# DAC.net
KiCad netlist of a schematic drawn in Altium Designer
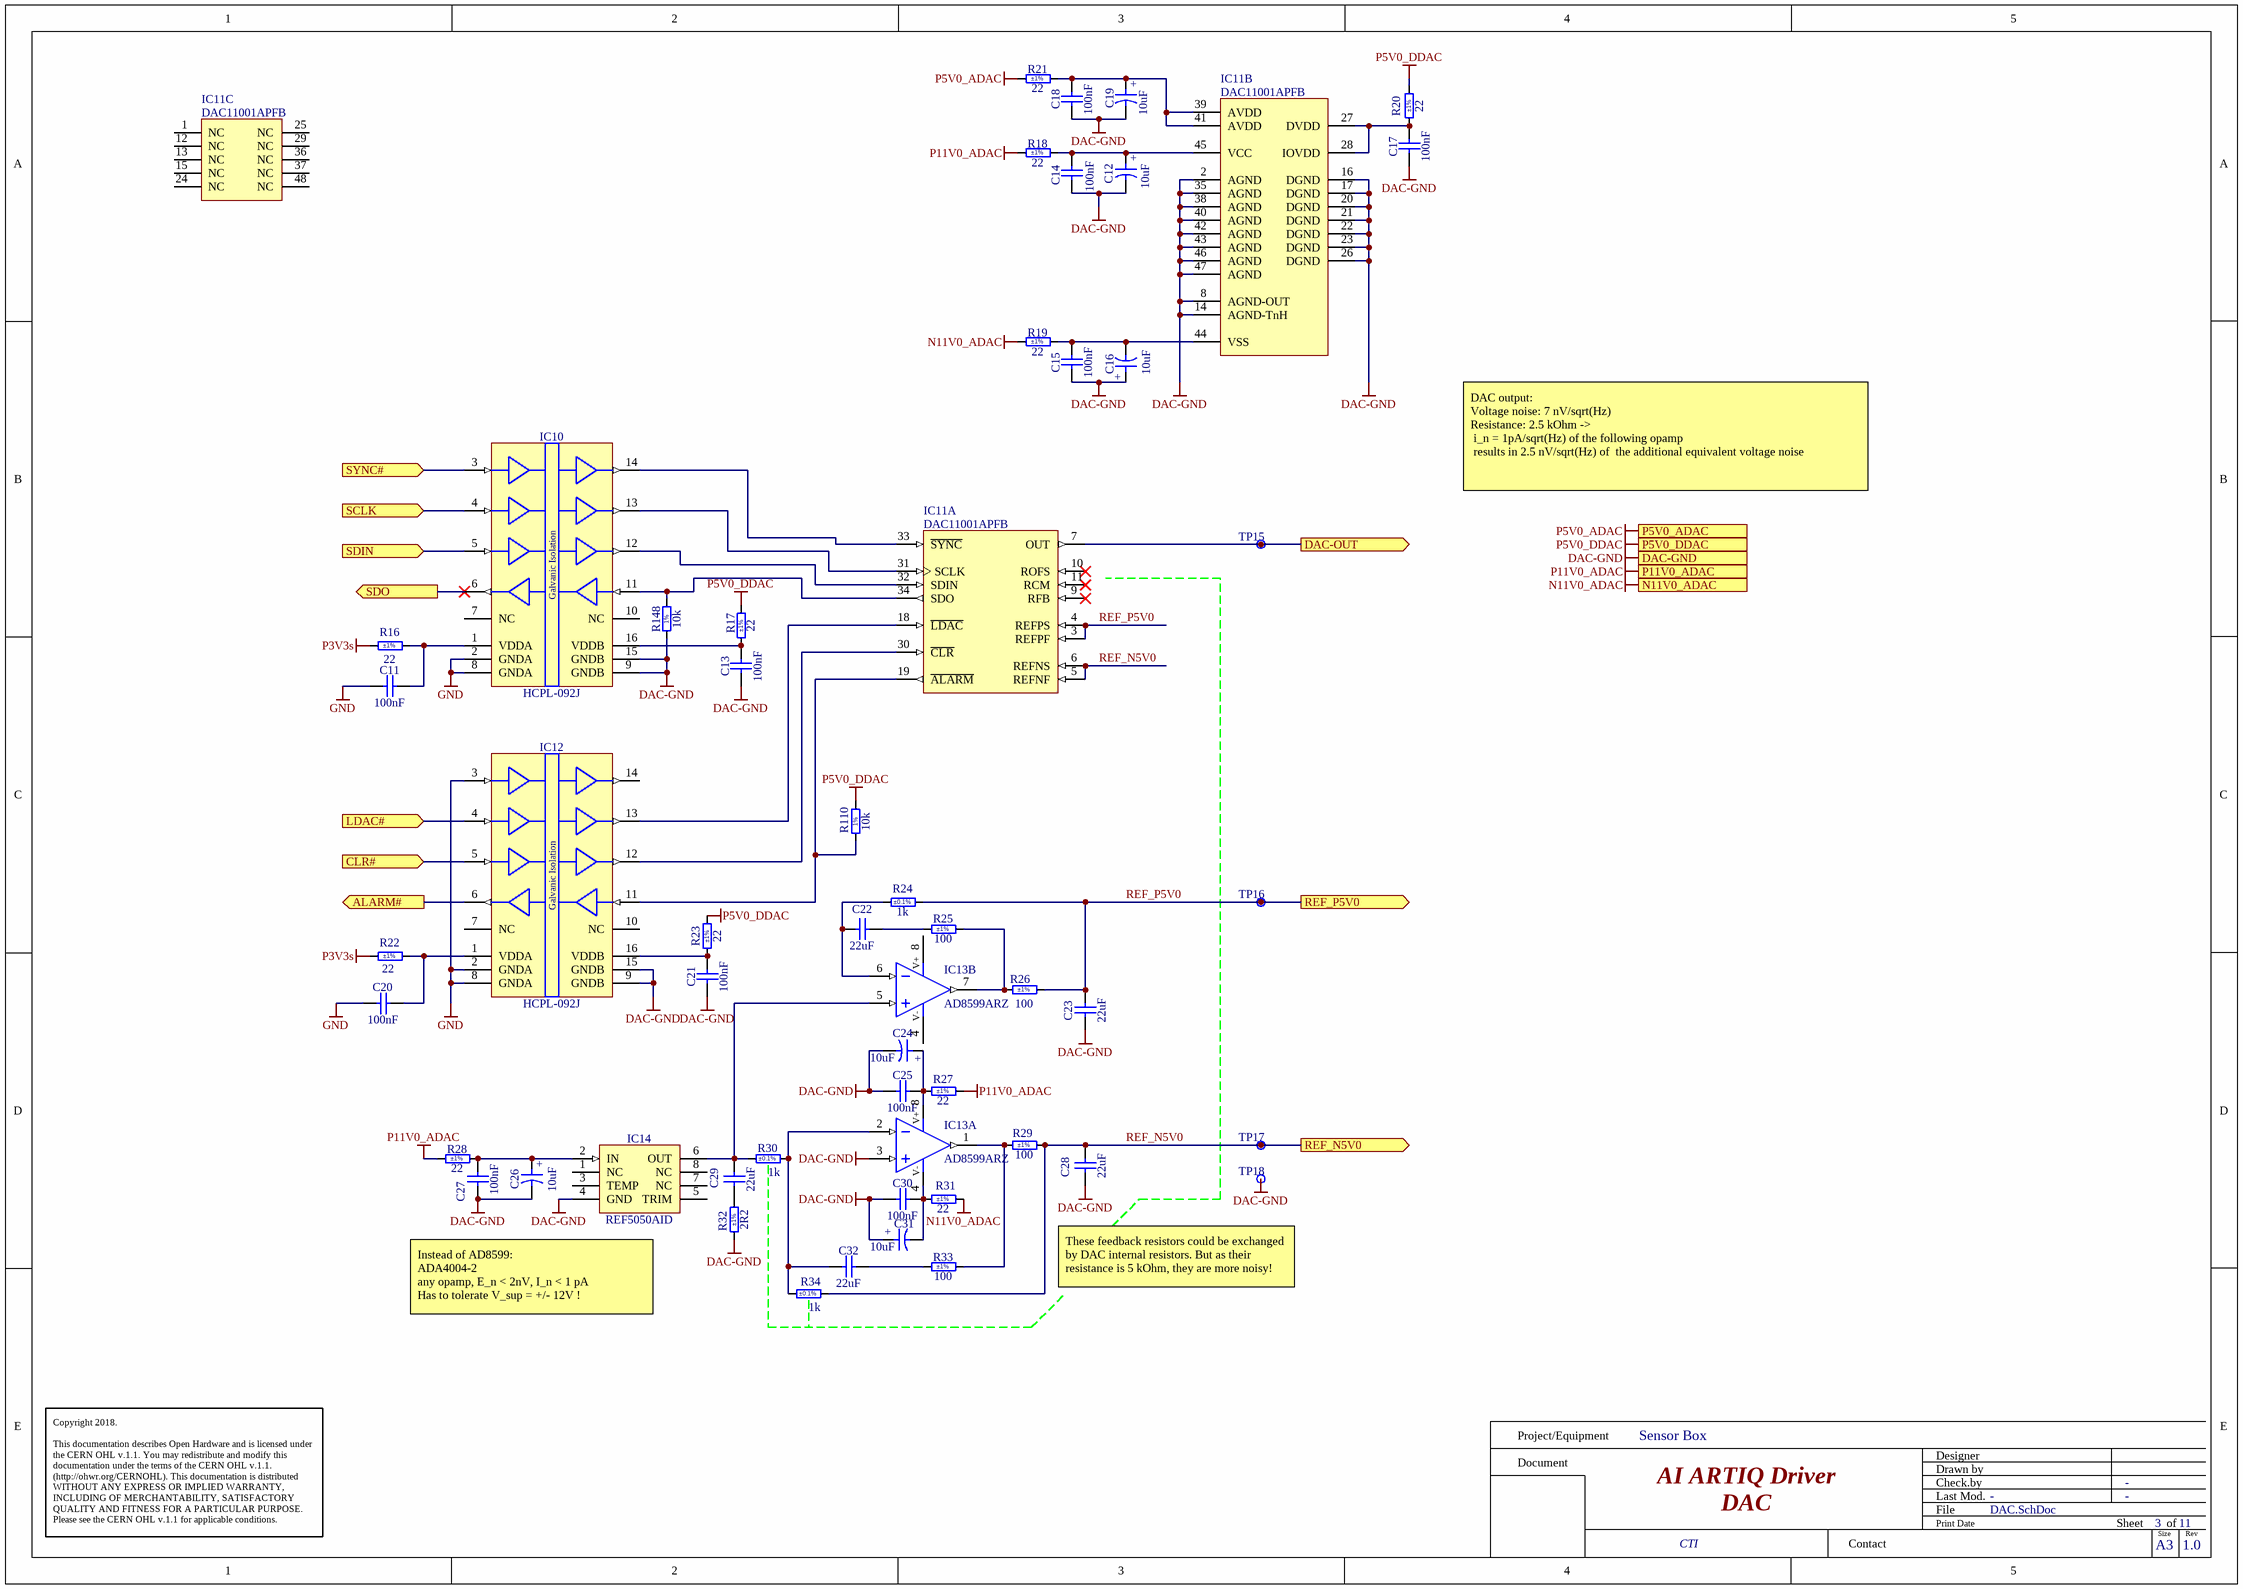
[diagram p0: DAC.SchDoc]

(export (version "E")
  (design (tool "Eeschema 10.0.6"))
  (components
    (comp (ref "C11")
      (value "100nF")
      (footprint "CAPC1608X87N")
      (description "Non-polarised capacitor")
      (fields
        (field (name "PART NUMBER") "CC0603_100NF_50V_10%_X7R")
        (field (name "VOLTAGE") "50V")
        (field (name "AUTHOR") "CERN DEM JLC")
      )
      (libsource (lib "Capacitors") (part "Capacitor - non polarized"))
    )
    (comp (ref "C12")
      (value "10uF")
      (footprint "CAPMP3528X210N")
      (description "Polarised capacitor")
      (fields
        (field (name "PART NUMBER") "CTE3528-21_10UF_20V_10%_AVX_TPSB106K020T0500")
        (field (name "VOLTAGE") "20V")
        (field (name "AUTHOR") "CERN DEM JLC")
      )
      (libsource (lib "Capacitors") (part "Capacitor - polarized"))
    )
    (comp (ref "C13")
      (value "100nF")
      (footprint "CAPC1608X87N")
      (description "Non-polarised capacitor")
      (fields
        (field (name "PART NUMBER") "CC0603_100NF_50V_10%_X7R")
        (field (name "VOLTAGE") "50V")
        (field (name "AUTHOR") "CERN DEM JLC")
      )
      (libsource (lib "Capacitors") (part "Capacitor - non polarized"))
    )
    (comp (ref "C14")
      (value "100nF")
      (footprint "CAPC1005X55N")
      (description "Non-polarised capacitor")
      (fields
        (field (name "PART NUMBER") "CC0402_100NF_50V_10%_X7R")
        (field (name "VOLTAGE") "50V")
        (field (name "AUTHOR") "CERN DEM MR")
      )
      (libsource (lib "Capacitors") (part "Capacitor - non polarized"))
    )
    (comp (ref "C15")
      (value "100nF")
      (footprint "CAPC1005X55N")
      (description "Non-polarised capacitor")
      (fields
        (field (name "PART NUMBER") "CC0402_100NF_50V_10%_X7R")
        (field (name "VOLTAGE") "50V")
        (field (name "AUTHOR") "CERN DEM MR")
      )
      (libsource (lib "Capacitors") (part "Capacitor - non polarized"))
    )
    (comp (ref "C16")
      (value "10uF")
      (footprint "CAPMP3528X210N")
      (description "Polarised capacitor")
      (fields
        (field (name "PART NUMBER") "CTE3528-21_10UF_20V_10%_AVX_TPSB106K020T0500")
        (field (name "VOLTAGE") "20V")
        (field (name "AUTHOR") "CERN DEM JLC")
      )
      (libsource (lib "Capacitors") (part "Capacitor - polarized"))
    )
    (comp (ref "C17")
      (value "100nF")
      (footprint "CAPC1005X55N")
      (description "Non-polarised capacitor")
      (fields
        (field (name "PART NUMBER") "CC0402_100NF_50V_10%_X7R")
        (field (name "VOLTAGE") "50V")
        (field (name "AUTHOR") "CERN DEM MR")
      )
      (libsource (lib "Capacitors") (part "Capacitor - non polarized"))
    )
    (comp (ref "C18")
      (value "100nF")
      (footprint "CAPC1005X55N")
      (description "Non-polarised capacitor")
      (fields
        (field (name "PART NUMBER") "CC0402_100NF_50V_10%_X7R")
        (field (name "VOLTAGE") "50V")
        (field (name "AUTHOR") "CERN DEM MR")
      )
      (libsource (lib "Capacitors") (part "Capacitor - non polarized"))
    )
    (comp (ref "C19")
      (value "10uF")
      (footprint "CAPMP3528X210N")
      (description "Polarised capacitor")
      (fields
        (field (name "PART NUMBER") "CTE3528-21_10UF_20V_10%_AVX_TPSB106K020T0500")
        (field (name "VOLTAGE") "20V")
        (field (name "AUTHOR") "CERN DEM JLC")
      )
      (libsource (lib "Capacitors") (part "Capacitor - polarized"))
    )
    (comp (ref "C20")
      (value "100nF")
      (footprint "CAPC1608X87N")
      (description "Non-polarised capacitor")
      (fields
        (field (name "PART NUMBER") "CC0603_100NF_50V_10%_X7R")
        (field (name "VOLTAGE") "50V")
        (field (name "AUTHOR") "CERN DEM JLC")
      )
      (libsource (lib "Capacitors") (part "Capacitor - non polarized"))
    )
    (comp (ref "C21")
      (value "100nF")
      (footprint "CAPC1608X87N")
      (description "Non-polarised capacitor")
      (fields
        (field (name "PART NUMBER") "CC0603_100NF_50V_10%_X7R")
        (field (name "VOLTAGE") "50V")
        (field (name "AUTHOR") "CERN DEM JLC")
      )
      (libsource (lib "Capacitors") (part "Capacitor - non polarized"))
    )
    (comp (ref "C22")
      (value "22uF")
      (footprint "CAPC2012X135N")
      (description "Non-polarised capacitor")
      (fields
        (field (name "PART NUMBER") "CC0805_22UF_16V_10%_X5R")
        (field (name "VOLTAGE") "16V")
        (field (name "AUTHOR") "CERN DEM JLC")
      )
      (libsource (lib "Capacitors") (part "Capacitor - non polarized"))
    )
    (comp (ref "C23")
      (value "22uF")
      (footprint "CAPC2012X135N")
      (description "Non-polarised capacitor")
      (fields
        (field (name "PART NUMBER") "CC0805_22UF_16V_10%_X5R")
        (field (name "VOLTAGE") "16V")
        (field (name "AUTHOR") "CERN DEM JLC")
      )
      (libsource (lib "Capacitors") (part "Capacitor - non polarized"))
    )
    (comp (ref "C24")
      (value "10uF")
      (footprint "CAPMP3528X210N")
      (description "Polarised capacitor")
      (fields
        (field (name "PART NUMBER") "CTE3528-21_10UF_20V_10%_AVX_TPSB106K020T0500")
        (field (name "VOLTAGE") "20V")
        (field (name "AUTHOR") "CERN DEM JLC")
      )
      (libsource (lib "Capacitors") (part "Capacitor - polarized"))
    )
    (comp (ref "C25")
      (value "100nF")
      (footprint "CAPC1608X87N")
      (description "Non-polarised capacitor")
      (fields
        (field (name "PART NUMBER") "CC0603_100NF_50V_10%_X7R")
        (field (name "VOLTAGE") "50V")
        (field (name "AUTHOR") "CERN DEM JLC")
      )
      (libsource (lib "Capacitors") (part "Capacitor - non polarized"))
    )
    (comp (ref "C26")
      (value "10uF")
      (footprint "CAPMP3528X210N")
      (description "Polarised capacitor")
      (fields
        (field (name "PART NUMBER") "CTE3528-21_10UF_20V_10%_AVX_TPSB106K020T0500")
        (field (name "VOLTAGE") "20V")
        (field (name "AUTHOR") "CERN DEM JLC")
      )
      (libsource (lib "Capacitors") (part "Capacitor - polarized"))
    )
    (comp (ref "C27")
      (value "100nF")
      (footprint "CAPC1608X87N")
      (description "Non-polarised capacitor")
      (fields
        (field (name "PART NUMBER") "CC0603_100NF_50V_10%_X7R")
        (field (name "VOLTAGE") "50V")
        (field (name "AUTHOR") "CERN DEM JLC")
      )
      (libsource (lib "Capacitors") (part "Capacitor - non polarized"))
    )
    (comp (ref "C28")
      (value "22uF")
      (footprint "CAPC2012X135N")
      (description "Non-polarised capacitor")
      (fields
        (field (name "PART NUMBER") "CC0805_22UF_16V_10%_X5R")
        (field (name "VOLTAGE") "16V")
        (field (name "AUTHOR") "CERN DEM JLC")
      )
      (libsource (lib "Capacitors") (part "Capacitor - non polarized"))
    )
    (comp (ref "C29")
      (value "22uF")
      (footprint "CAPC2012X135N")
      (description "Non-polarised capacitor")
      (fields
        (field (name "PART NUMBER") "CC0805_22UF_16V_10%_X5R")
        (field (name "VOLTAGE") "16V")
        (field (name "AUTHOR") "CERN DEM JLC")
      )
      (libsource (lib "Capacitors") (part "Capacitor - non polarized"))
    )
    (comp (ref "C30")
      (value "100nF")
      (footprint "CAPC1608X87N")
      (description "Non-polarised capacitor")
      (fields
        (field (name "PART NUMBER") "CC0603_100NF_50V_10%_X7R")
        (field (name "VOLTAGE") "50V")
        (field (name "AUTHOR") "CERN DEM JLC")
      )
      (libsource (lib "Capacitors") (part "Capacitor - non polarized"))
    )
    (comp (ref "C31")
      (value "10uF")
      (footprint "CAPMP3528X210N")
      (description "Polarised capacitor")
      (fields
        (field (name "PART NUMBER") "CTE3528-21_10UF_20V_10%_AVX_TPSB106K020T0500")
        (field (name "VOLTAGE") "20V")
        (field (name "AUTHOR") "CERN DEM JLC")
      )
      (libsource (lib "Capacitors") (part "Capacitor - polarized"))
    )
    (comp (ref "C32")
      (value "22uF")
      (footprint "CAPC2012X135N")
      (description "Non-polarised capacitor")
      (fields
        (field (name "PART NUMBER") "CC0805_22UF_16V_10%_X5R")
        (field (name "VOLTAGE") "16V")
        (field (name "AUTHOR") "CERN DEM JLC")
      )
      (libsource (lib "Capacitors") (part "Capacitor - non polarized"))
    )
    (comp (ref "IC10")
      (value "HCPL-092J")
      (footprint "HCPL-092J")
      (description "High Speed Digital Isolators Quad, 1/3, Bidirectional")
      (fields (field (name "MANUFACTURER") "BROADCOM") (field (name "AUTHOR") "CERN DEM HF"))
      (libsource (lib "ICs And Semiconductors") (part "HCPL-092J"))
    )
    (comp (ref "IC11")
      (value "DAC11001APFB")
      (footprint "QFP50P900X900X120-48N")
      (fields (field (name "MANUFACTURER") "TEXAS INSTRUMENTS") (field (name "AUTHOR") "CERN DEM HF"))
      (libsource (lib "ICs And Semiconductors") (part "DAC11001APFB"))
    )
    (comp (ref "IC12")
      (value "HCPL-092J")
      (footprint "HCPL-092J")
      (description "High Speed Digital Isolators Quad, 1/3, Bidirectional")
      (fields (field (name "MANUFACTURER") "BROADCOM") (field (name "AUTHOR") "CERN DEM HF"))
      (libsource (lib "ICs And Semiconductors") (part "HCPL-092J"))
    )
    (comp (ref "IC13")
      (value "AD8599ARZ")
      (footprint "SOIC127P600X175-8N")
      (description "Dual Operational Amplifier")
      (fields
        (field (name "MANUFACTURER") "ANALOG DEVICES")
        (field (name "MANUFACTURER PART NUMBER") "AD8599AR")
        (field (name "AUTHOR") "CERN DEM BC")
      )
      (libsource (lib "ICs And Semiconductors") (part "Operational Amplifier x2 Type1"))
    )
    (comp (ref "IC14")
      (value "REF5050AID")
      (footprint "SOIC127P600X175-8N")
      (description "Low-Noise, Very Low Drift, Precision Voltage Reference")
      (fields (field (name "MANUFACTURER") "TEXAS INSTRUMENTS") (field (name "AUTHOR") "CERN DEM HF"))
      (libsource (lib "ICs And Semiconductors") (part "REF50xx"))
    )
    (comp (ref "R16")
      (value "22")
      (footprint "RESC1608X55N")
      (description "Resistor - 1%")
      (fields
        (field (name "TOLERANCE") "±1%")
        (field (name "PART NUMBER") "R0603_22R_1%_0.1W_100PPM")
        (field (name "POWER") "0.1W")
        (field (name "AUTHOR") "CERN DEM JLC")
      )
      (libsource (lib "Resistors") (part "Resistor - 1%"))
    )
    (comp (ref "R17")
      (value "22")
      (footprint "RESC1608X55N")
      (description "Resistor - 1%")
      (fields
        (field (name "TOLERANCE") "±1%")
        (field (name "PART NUMBER") "R0603_22R_1%_0.1W_100PPM")
        (field (name "POWER") "0.1W")
        (field (name "AUTHOR") "CERN DEM JLC")
      )
      (libsource (lib "Resistors") (part "Resistor - 1%"))
    )
    (comp (ref "R18")
      (value "22")
      (footprint "RESC1608X55N")
      (description "Resistor - 1%")
      (fields
        (field (name "TOLERANCE") "±1%")
        (field (name "PART NUMBER") "R0603_22R_1%_0.1W_100PPM")
        (field (name "POWER") "0.1W")
        (field (name "AUTHOR") "CERN DEM JLC")
      )
      (libsource (lib "Resistors") (part "Resistor - 1%"))
    )
    (comp (ref "R19")
      (value "22")
      (footprint "RESC1608X55N")
      (description "Resistor - 1%")
      (fields
        (field (name "TOLERANCE") "±1%")
        (field (name "PART NUMBER") "R0603_22R_1%_0.1W_100PPM")
        (field (name "POWER") "0.1W")
        (field (name "AUTHOR") "CERN DEM JLC")
      )
      (libsource (lib "Resistors") (part "Resistor - 1%"))
    )
    (comp (ref "R20")
      (value "22")
      (footprint "RESC1608X55N")
      (description "Resistor - 1%")
      (fields
        (field (name "TOLERANCE") "±1%")
        (field (name "PART NUMBER") "R0603_22R_1%_0.1W_100PPM")
        (field (name "POWER") "0.1W")
        (field (name "AUTHOR") "CERN DEM JLC")
      )
      (libsource (lib "Resistors") (part "Resistor - 1%"))
    )
    (comp (ref "R21")
      (value "22")
      (footprint "RESC1608X55N")
      (description "Resistor - 1%")
      (fields
        (field (name "TOLERANCE") "±1%")
        (field (name "PART NUMBER") "R0603_22R_1%_0.1W_100PPM")
        (field (name "POWER") "0.1W")
        (field (name "AUTHOR") "CERN DEM JLC")
      )
      (libsource (lib "Resistors") (part "Resistor - 1%"))
    )
    (comp (ref "R22")
      (value "22")
      (footprint "RESC1608X55N")
      (description "Resistor - 1%")
      (fields
        (field (name "TOLERANCE") "±1%")
        (field (name "PART NUMBER") "R0603_22R_1%_0.1W_100PPM")
        (field (name "POWER") "0.1W")
        (field (name "AUTHOR") "CERN DEM JLC")
      )
      (libsource (lib "Resistors") (part "Resistor - 1%"))
    )
    (comp (ref "R23")
      (value "22")
      (footprint "RESC1608X55N")
      (description "Resistor - 1%")
      (fields
        (field (name "TOLERANCE") "±1%")
        (field (name "PART NUMBER") "R0603_22R_1%_0.1W_100PPM")
        (field (name "POWER") "0.1W")
        (field (name "AUTHOR") "CERN DEM JLC")
      )
      (libsource (lib "Resistors") (part "Resistor - 1%"))
    )
    (comp (ref "R24")
      (value "1k")
      (footprint "RESC1608X64N")
      (description "Resistor - 0.1%")
      (fields
        (field (name "TOLERANCE") "±0.1%")
        (field (name "PART NUMBER") "R0603_1K_0.1%_0.1W_25PPM")
        (field (name "POWER") "0.1W")
        (field (name "AUTHOR") "CERN DEM JLC")
      )
      (libsource (lib "Resistors") (part "Resistor - 0.1%"))
    )
    (comp (ref "R25")
      (value "100")
      (footprint "RESC1608X55N")
      (description "Resistor - 1%")
      (fields
        (field (name "TOLERANCE") "±1%")
        (field (name "PART NUMBER") "R0603_100R_1%_0.1W_100PPM")
        (field (name "POWER") "0.1W")
        (field (name "AUTHOR") "CERN DEM JLC")
      )
      (libsource (lib "Resistors") (part "Resistor - 1%"))
    )
    (comp (ref "R26")
      (value "100")
      (footprint "RESC1608X55N")
      (description "Resistor - 1%")
      (fields
        (field (name "TOLERANCE") "±1%")
        (field (name "PART NUMBER") "R0603_100R_1%_0.1W_100PPM")
        (field (name "POWER") "0.1W")
        (field (name "AUTHOR") "CERN DEM JLC")
      )
      (libsource (lib "Resistors") (part "Resistor - 1%"))
    )
    (comp (ref "R27")
      (value "22")
      (footprint "RESC1608X55N")
      (description "Resistor - 1%")
      (fields
        (field (name "TOLERANCE") "±1%")
        (field (name "PART NUMBER") "R0603_22R_1%_0.1W_100PPM")
        (field (name "POWER") "0.1W")
        (field (name "AUTHOR") "CERN DEM JLC")
      )
      (libsource (lib "Resistors") (part "Resistor - 1%"))
    )
    (comp (ref "R28")
      (value "22")
      (footprint "RESC1608X55N")
      (description "Resistor - 1%")
      (fields
        (field (name "TOLERANCE") "±1%")
        (field (name "PART NUMBER") "R0603_22R_1%_0.1W_100PPM")
        (field (name "POWER") "0.1W")
        (field (name "AUTHOR") "CERN DEM JLC")
      )
      (libsource (lib "Resistors") (part "Resistor - 1%"))
    )
    (comp (ref "R29")
      (value "100")
      (footprint "RESC1608X55N")
      (description "Resistor - 1%")
      (fields
        (field (name "TOLERANCE") "±1%")
        (field (name "PART NUMBER") "R0603_100R_1%_0.1W_100PPM")
        (field (name "POWER") "0.1W")
        (field (name "AUTHOR") "CERN DEM JLC")
      )
      (libsource (lib "Resistors") (part "Resistor - 1%"))
    )
    (comp (ref "R30")
      (value "1k")
      (footprint "RESC1608X64N")
      (description "Resistor - 0.1%")
      (fields
        (field (name "TOLERANCE") "±0.1%")
        (field (name "PART NUMBER") "R0603_1K_0.1%_0.1W_25PPM")
        (field (name "POWER") "0.1W")
        (field (name "AUTHOR") "CERN DEM JLC")
      )
      (libsource (lib "Resistors") (part "Resistor - 0.1%"))
    )
    (comp (ref "R31")
      (value "22")
      (footprint "RESC1608X55N")
      (description "Resistor - 1%")
      (fields
        (field (name "TOLERANCE") "±1%")
        (field (name "PART NUMBER") "R0603_22R_1%_0.1W_100PPM")
        (field (name "POWER") "0.1W")
        (field (name "AUTHOR") "CERN DEM JLC")
      )
      (libsource (lib "Resistors") (part "Resistor - 1%"))
    )
    (comp (ref "R32")
      (value "2R2")
      (footprint "RESC1608X55N")
      (description "Resistor - 1%")
      (fields
        (field (name "TOLERANCE") "±1%")
        (field (name "PART NUMBER") "R0603_2R2_1%_0.1W_200PPM")
        (field (name "POWER") "0.1W")
        (field (name "AUTHOR") "CERN DEM JLC")
      )
      (libsource (lib "Resistors") (part "Resistor - 1%"))
    )
    (comp (ref "R33")
      (value "100")
      (footprint "RESC1608X55N")
      (description "Resistor - 1%")
      (fields
        (field (name "TOLERANCE") "±1%")
        (field (name "PART NUMBER") "R0603_100R_1%_0.1W_100PPM")
        (field (name "POWER") "0.1W")
        (field (name "AUTHOR") "CERN DEM JLC")
      )
      (libsource (lib "Resistors") (part "Resistor - 1%"))
    )
    (comp (ref "R34")
      (value "1k")
      (footprint "RESC1608X64N")
      (description "Resistor - 0.1%")
      (fields
        (field (name "TOLERANCE") "±0.1%")
        (field (name "PART NUMBER") "R0603_1K_0.1%_0.1W_25PPM")
        (field (name "POWER") "0.1W")
        (field (name "AUTHOR") "CERN DEM JLC")
      )
      (libsource (lib "Resistors") (part "Resistor - 0.1%"))
    )
    (comp (ref "R110")
      (value "10k")
      (footprint "RESC1608X55N")
      (description "Resistor - 1%")
      (fields
        (field (name "PART NUMBER") "R0603_10K_1%_0.1W_100PPM")
        (field (name "POWER") "0.1W")
        (field (name "AUTHOR") "CERN DEM JLC")
      )
      (libsource (lib "Resistors") (part "Resistor - 1%"))
    )
    (comp (ref "R148")
      (value "10k")
      (footprint "RESC1608X55N")
      (description "Resistor - 1%")
      (fields
        (field (name "PART NUMBER") "R0603_10K_1%_0.1W_100PPM")
        (field (name "POWER") "0.1W")
        (field (name "AUTHOR") "CERN DEM JLC")
      )
      (libsource (lib "Resistors") (part "Resistor - 1%"))
    )
    (comp (ref "TP15")
      (value "Test Point")
      (footprint "TPS127")
      (fields (field (name "PART NUMBER") "SMD_PAD_1.27X1.27MM") (field (name "AUTHOR") "CERN DEM JLC"))
      (libsource (lib "Eletro-mechanical") (part "Test Point"))
    )
    (comp (ref "TP16")
      (value "Test Point")
      (footprint "TPS127")
      (fields (field (name "PART NUMBER") "SMD_PAD_1.27X1.27MM") (field (name "AUTHOR") "CERN DEM JLC"))
      (libsource (lib "Eletro-mechanical") (part "Test Point"))
    )
    (comp (ref "TP17")
      (value "Test Point")
      (footprint "TPS127")
      (fields (field (name "PART NUMBER") "SMD_PAD_1.27X1.27MM") (field (name "AUTHOR") "CERN DEM JLC"))
      (libsource (lib "Eletro-mechanical") (part "Test Point"))
    )
    (comp (ref "TP18")
      (value "Test Point")
      (footprint "TPS127")
      (fields (field (name "PART NUMBER") "SMD_PAD_1.27X1.27MM") (field (name "AUTHOR") "CERN DEM JLC"))
      (libsource (lib "Eletro-mechanical") (part "Test Point"))
    )
  )
  (nets
    (net (code "1") (name "/ALARM#") (class "Default")
      (node (ref "IC12") (pin "6") (pinfunction "IN4_6") (pintype "output"))
    )
    (net (code "2") (name "/CLR#") (class "Default")
      (node (ref "IC12") (pin "5") (pinfunction "IN3_5") (pintype "input"))
    )
    (net (code "3") (name "/DAC-OUT") (class "Default")
      (node (ref "IC11") (pin "7") (pinfunction "OUT_7") (pintype "output"))
      (node (ref "TP15") (pin "1") (pinfunction "1_1") (pintype "bidirectional"))
    )
    (net (code "4") (name "/LDAC#") (class "Default")
      (node (ref "IC12") (pin "4") (pinfunction "IN2_4") (pintype "input"))
    )
    (net (code "5") (name "/REF_N5V0") (class "Default")
      (node (ref "C28") (pin "2") (pinfunction "2_2") (pintype "passive"))
      (node (ref "IC11") (pin "5") (pinfunction "REFNF_5") (pintype "input"))
      (node (ref "IC11") (pin "6") (pinfunction "REFNS_6") (pintype "input"))
      (node (ref "R29") (pin "2") (pinfunction "2_2") (pintype "passive"))
      (node (ref "R34") (pin "2") (pinfunction "2_2") (pintype "passive"))
      (node (ref "TP17") (pin "1") (pinfunction "1_1") (pintype "bidirectional"))
    )
    (net (code "6") (name "/REF_P5V0") (class "Default")
      (node (ref "C23") (pin "2") (pinfunction "2_2") (pintype "passive"))
      (node (ref "IC11") (pin "3") (pinfunction "REFPF_3") (pintype "input"))
      (node (ref "IC11") (pin "4") (pinfunction "REFPS_4") (pintype "input"))
      (node (ref "R24") (pin "2") (pinfunction "2_2") (pintype "passive"))
      (node (ref "R26") (pin "2") (pinfunction "2_2") (pintype "passive"))
      (node (ref "TP16") (pin "1") (pinfunction "1_1") (pintype "bidirectional"))
    )
    (net (code "7") (name "/SCLK") (class "Default")
      (node (ref "IC10") (pin "4") (pinfunction "IN2_4") (pintype "input"))
    )
    (net (code "8") (name "/SDIN") (class "Default")
      (node (ref "IC10") (pin "5") (pinfunction "IN3_5") (pintype "input"))
    )
    (net (code "9") (name "/SDO") (class "Default")
      (node (ref "IC10") (pin "6") (pinfunction "IN4_6") (pintype "output+no_connect"))
    )
    (net (code "10") (name "/SYNC#") (class "Default")
      (node (ref "IC10") (pin "3") (pinfunction "IN1_3") (pintype "input"))
    )
    (net (code "11") (name "DAC-GND") (class "Default")
      (node (ref "C12") (pin "2") (pinfunction "2_2") (pintype "passive"))
      (node (ref "C13") (pin "1") (pinfunction "1_1") (pintype "passive"))
      (node (ref "C14") (pin "2") (pinfunction "2_2") (pintype "passive"))
      (node (ref "C15") (pin "1") (pinfunction "1_1") (pintype "passive"))
      (node (ref "C16") (pin "1") (pinfunction "1_1") (pintype "passive"))
      (node (ref "C17") (pin "1") (pinfunction "1_1") (pintype "passive"))
      (node (ref "C18") (pin "1") (pinfunction "1_1") (pintype "passive"))
      (node (ref "C19") (pin "2") (pinfunction "2_2") (pintype "passive"))
      (node (ref "C21") (pin "1") (pinfunction "1_1") (pintype "passive"))
      (node (ref "C23") (pin "1") (pinfunction "1_1") (pintype "passive"))
      (node (ref "C24") (pin "2") (pinfunction "2_2") (pintype "passive"))
      (node (ref "C25") (pin "1") (pinfunction "1_1") (pintype "passive"))
      (node (ref "C26") (pin "2") (pinfunction "2_2") (pintype "passive"))
      (node (ref "C27") (pin "1") (pinfunction "1_1") (pintype "passive"))
      (node (ref "C28") (pin "1") (pinfunction "1_1") (pintype "passive"))
      (node (ref "C30") (pin "1") (pinfunction "1_1") (pintype "passive"))
      (node (ref "C31") (pin "1") (pinfunction "1_1") (pintype "passive"))
      (node (ref "IC10") (pin "15") (pinfunction "GNDB_15") (pintype "power_in"))
      (node (ref "IC10") (pin "9") (pinfunction "GNDB_9") (pintype "power_in"))
      (node (ref "IC11") (pin "14") (pinfunction "AGND-TnH_14") (pintype "power_in"))
      (node (ref "IC11") (pin "16") (pinfunction "DGND_16") (pintype "power_in"))
      (node (ref "IC11") (pin "17") (pinfunction "DGND_17") (pintype "power_in"))
      (node (ref "IC11") (pin "2") (pinfunction "AGND_2") (pintype "power_in"))
      (node (ref "IC11") (pin "20") (pinfunction "DGND_20") (pintype "power_in"))
      (node (ref "IC11") (pin "21") (pinfunction "DGND_21") (pintype "power_in"))
      (node (ref "IC11") (pin "22") (pinfunction "DGND_22") (pintype "power_in"))
      (node (ref "IC11") (pin "23") (pinfunction "DGND_23") (pintype "power_in"))
      (node (ref "IC11") (pin "26") (pinfunction "DGND_26") (pintype "power_in"))
      (node (ref "IC11") (pin "35") (pinfunction "AGND_35") (pintype "power_in"))
      (node (ref "IC11") (pin "38") (pinfunction "AGND_38") (pintype "power_in"))
      (node (ref "IC11") (pin "40") (pinfunction "AGND_40") (pintype "power_in"))
      (node (ref "IC11") (pin "42") (pinfunction "AGND_42") (pintype "power_in"))
      (node (ref "IC11") (pin "43") (pinfunction "AGND_43") (pintype "power_in"))
      (node (ref "IC11") (pin "46") (pinfunction "AGND_46") (pintype "power_in"))
      (node (ref "IC11") (pin "47") (pinfunction "AGND_47") (pintype "power_in"))
      (node (ref "IC11") (pin "8") (pinfunction "AGND-OUT_8") (pintype "power_in"))
      (node (ref "IC12") (pin "15") (pinfunction "GNDB_15") (pintype "power_in"))
      (node (ref "IC12") (pin "9") (pinfunction "GNDB_9") (pintype "power_in"))
      (node (ref "IC13") (pin "3") (pinfunction "IN+_3") (pintype "input"))
      (node (ref "IC14") (pin "4") (pinfunction "GND_4") (pintype "power_in"))
      (node (ref "R148") (pin "1") (pinfunction "1_1") (pintype "passive"))
      (node (ref "R32") (pin "1") (pinfunction "1_1") (pintype "passive"))
      (node (ref "TP18") (pin "1") (pinfunction "1_1") (pintype "bidirectional"))
    )
    (net (code "12") (name "GND") (class "Default")
      (node (ref "C11") (pin "1") (pinfunction "1_1") (pintype "passive"))
      (node (ref "C20") (pin "1") (pinfunction "1_1") (pintype "passive"))
      (node (ref "IC10") (pin "2") (pinfunction "GNDA_2") (pintype "power_in"))
      (node (ref "IC10") (pin "8") (pinfunction "GNDA_8") (pintype "power_in"))
      (node (ref "IC12") (pin "2") (pinfunction "GNDA_2") (pintype "power_in"))
      (node (ref "IC12") (pin "3") (pinfunction "IN1_3") (pintype "input"))
      (node (ref "IC12") (pin "8") (pinfunction "GNDA_8") (pintype "power_in"))
    )
    (net (code "13") (name "N11V0_ADAC") (class "Default")
      (node (ref "R19") (pin "1") (pinfunction "1_1") (pintype "passive"))
      (node (ref "R31") (pin "2") (pinfunction "2_2") (pintype "passive"))
    )
    (net (code "14") (name "Net-(C18-Pad2)") (class "Default")
      (node (ref "C18") (pin "2") (pinfunction "2_2") (pintype "passive"))
      (node (ref "C19") (pin "1") (pinfunction "1_1") (pintype "passive"))
      (node (ref "IC11") (pin "39") (pinfunction "AVDD_39") (pintype "power_in"))
      (node (ref "IC11") (pin "41") (pinfunction "AVDD_41") (pintype "power_in"))
      (node (ref "R21") (pin "2") (pinfunction "2_2") (pintype "passive"))
    )
    (net (code "15") (name "Net-(C22-Pad2)") (class "Default")
      (node (ref "C22") (pin "2") (pinfunction "2_2") (pintype "passive"))
      (node (ref "R25") (pin "1") (pinfunction "1_1") (pintype "passive"))
    )
    (net (code "16") (name "Net-(C29-Pad1)") (class "Default")
      (node (ref "C29") (pin "1") (pinfunction "1_1") (pintype "passive"))
      (node (ref "R32") (pin "2") (pinfunction "2_2") (pintype "passive"))
    )
    (net (code "17") (name "Net-(C32-Pad2)") (class "Default")
      (node (ref "C32") (pin "2") (pinfunction "2_2") (pintype "passive"))
      (node (ref "R33") (pin "1") (pinfunction "1_1") (pintype "passive"))
    )
    (net (code "18") (name "Net-(IC10-OUT1)") (class "Default")
      (node (ref "IC10") (pin "14") (pinfunction "OUT1_14") (pintype "output"))
      (node (ref "IC11") (pin "33") (pinfunction "~{SYNC}_33") (pintype "input"))
    )
    (net (code "19") (name "Net-(IC10-OUT2)") (class "Default")
      (node (ref "IC10") (pin "13") (pinfunction "OUT2_13") (pintype "output"))
      (node (ref "IC11") (pin "31") (pinfunction "SCLK_31") (pintype "input"))
    )
    (net (code "20") (name "Net-(IC10-OUT3)") (class "Default")
      (node (ref "IC10") (pin "12") (pinfunction "OUT3_12") (pintype "output"))
      (node (ref "IC11") (pin "32") (pinfunction "SDIN_32") (pintype "input"))
    )
    (net (code "21") (name "Net-(IC10-OUT4)") (class "Default")
      (node (ref "IC10") (pin "11") (pinfunction "OUT4_11") (pintype "input"))
      (node (ref "IC11") (pin "34") (pinfunction "SDO_34") (pintype "output"))
      (node (ref "R148") (pin "2") (pinfunction "2_2") (pintype "passive"))
    )
    (net (code "22") (name "Net-(IC10-VDDA)") (class "Default")
      (node (ref "C11") (pin "2") (pinfunction "2_2") (pintype "passive"))
      (node (ref "IC10") (pin "1") (pinfunction "VDDA_1") (pintype "power_in"))
      (node (ref "R16") (pin "1") (pinfunction "1_1") (pintype "passive"))
    )
    (net (code "23") (name "Net-(IC10-VDDB)") (class "Default")
      (node (ref "C13") (pin "2") (pinfunction "2_2") (pintype "passive"))
      (node (ref "IC10") (pin "16") (pinfunction "VDDB_16") (pintype "power_in"))
      (node (ref "R17") (pin "1") (pinfunction "1_1") (pintype "passive"))
    )
    (net (code "24") (name "Net-(IC11A-~{ALARM})") (class "Default")
      (node (ref "IC11") (pin "19") (pinfunction "~{ALARM}_19") (pintype "output"))
      (node (ref "IC12") (pin "11") (pinfunction "OUT4_11") (pintype "input"))
      (node (ref "R110") (pin "1") (pinfunction "1_1") (pintype "passive"))
    )
    (net (code "25") (name "Net-(IC11A-~{CLR})") (class "Default")
      (node (ref "IC11") (pin "30") (pinfunction "~{CLR}_30") (pintype "input"))
      (node (ref "IC12") (pin "12") (pinfunction "OUT3_12") (pintype "output"))
    )
    (net (code "26") (name "Net-(IC11A-~{LDAC})") (class "Default")
      (node (ref "IC11") (pin "18") (pinfunction "~{LDAC}_18") (pintype "input"))
      (node (ref "IC12") (pin "13") (pinfunction "OUT2_13") (pintype "output"))
    )
    (net (code "27") (name "Net-(IC11B-DVDD)") (class "Default")
      (node (ref "C17") (pin "2") (pinfunction "2_2") (pintype "passive"))
      (node (ref "IC11") (pin "27") (pinfunction "DVDD_27") (pintype "power_in"))
      (node (ref "IC11") (pin "28") (pinfunction "IOVDD_28") (pintype "power_in"))
      (node (ref "R20") (pin "1") (pinfunction "1_1") (pintype "passive"))
    )
    (net (code "28") (name "Net-(IC11B-VCC)") (class "Default")
      (node (ref "C12") (pin "1") (pinfunction "1_1") (pintype "passive"))
      (node (ref "C14") (pin "1") (pinfunction "1_1") (pintype "passive"))
      (node (ref "IC11") (pin "45") (pinfunction "VCC_45") (pintype "power_in"))
      (node (ref "R18") (pin "2") (pinfunction "2_2") (pintype "passive"))
    )
    (net (code "29") (name "Net-(IC11B-VSS)") (class "Default")
      (node (ref "C15") (pin "2") (pinfunction "2_2") (pintype "passive"))
      (node (ref "C16") (pin "2") (pinfunction "2_2") (pintype "passive"))
      (node (ref "IC11") (pin "44") (pinfunction "VSS_44") (pintype "power_in"))
      (node (ref "R19") (pin "2") (pinfunction "2_2") (pintype "passive"))
    )
    (net (code "30") (name "Net-(IC12-VDDA)") (class "Default")
      (node (ref "C20") (pin "2") (pinfunction "2_2") (pintype "passive"))
      (node (ref "IC12") (pin "1") (pinfunction "VDDA_1") (pintype "power_in"))
      (node (ref "R22") (pin "1") (pinfunction "1_1") (pintype "passive"))
    )
    (net (code "31") (name "Net-(IC12-VDDB)") (class "Default")
      (node (ref "C21") (pin "2") (pinfunction "2_2") (pintype "passive"))
      (node (ref "IC12") (pin "16") (pinfunction "VDDB_16") (pintype "power_in"))
      (node (ref "R23") (pin "1") (pinfunction "1_1") (pintype "passive"))
    )
    (net (code "32") (name "Net-(IC13A-IN-)") (class "Default")
      (node (ref "C32") (pin "1") (pinfunction "1_1") (pintype "passive"))
      (node (ref "IC13") (pin "2") (pinfunction "IN-_2") (pintype "input"))
      (node (ref "R30") (pin "2") (pinfunction "2_2") (pintype "passive"))
      (node (ref "R34") (pin "1") (pinfunction "1_1") (pintype "passive"))
    )
    (net (code "33") (name "Net-(IC13A-OUT)") (class "Default")
      (node (ref "IC13") (pin "1") (pinfunction "OUT_1") (pintype "output"))
      (node (ref "R29") (pin "1") (pinfunction "1_1") (pintype "passive"))
      (node (ref "R33") (pin "2") (pinfunction "2_2") (pintype "passive"))
    )
    (net (code "34") (name "Net-(IC13A-V+)") (class "Default")
      (node (ref "C24") (pin "1") (pinfunction "1_1") (pintype "passive"))
      (node (ref "C25") (pin "2") (pinfunction "2_2") (pintype "passive"))
      (node (ref "IC13") (pin "8") (pinfunction "V+_8") (pintype "power_in"))
      (node (ref "R27") (pin "1") (pinfunction "1_1") (pintype "passive"))
    )
    (net (code "35") (name "Net-(IC13A-V-)") (class "Default")
      (node (ref "C30") (pin "2") (pinfunction "2_2") (pintype "passive"))
      (node (ref "C31") (pin "2") (pinfunction "2_2") (pintype "passive"))
      (node (ref "IC13") (pin "4") (pinfunction "V-_4") (pintype "power_in"))
      (node (ref "R31") (pin "1") (pinfunction "1_1") (pintype "passive"))
    )
    (net (code "36") (name "Net-(IC13B-IN+)") (class "Default")
      (node (ref "C29") (pin "2") (pinfunction "2_2") (pintype "passive"))
      (node (ref "IC13") (pin "5") (pinfunction "IN+_5") (pintype "input"))
      (node (ref "IC14") (pin "6") (pinfunction "OUT_6") (pintype "power_in"))
      (node (ref "R30") (pin "1") (pinfunction "1_1") (pintype "passive"))
    )
    (net (code "37") (name "Net-(IC13B-IN-)") (class "Default")
      (node (ref "C22") (pin "1") (pinfunction "1_1") (pintype "passive"))
      (node (ref "IC13") (pin "6") (pinfunction "IN-_6") (pintype "input"))
      (node (ref "R24") (pin "1") (pinfunction "1_1") (pintype "passive"))
    )
    (net (code "38") (name "Net-(IC13B-OUT)") (class "Default")
      (node (ref "IC13") (pin "7") (pinfunction "OUT_7") (pintype "output"))
      (node (ref "R25") (pin "2") (pinfunction "2_2") (pintype "passive"))
      (node (ref "R26") (pin "1") (pinfunction "1_1") (pintype "passive"))
    )
    (net (code "39") (name "Net-(IC14-IN)") (class "Default")
      (node (ref "C26") (pin "1") (pinfunction "1_1") (pintype "passive"))
      (node (ref "C27") (pin "2") (pinfunction "2_2") (pintype "passive"))
      (node (ref "IC14") (pin "2") (pinfunction "IN_2") (pintype "input"))
      (node (ref "R28") (pin "2") (pinfunction "2_2") (pintype "passive"))
    )
    (net (code "40") (name "P3V3s") (class "Default")
      (node (ref "R16") (pin "2") (pinfunction "2_2") (pintype "passive"))
      (node (ref "R22") (pin "2") (pinfunction "2_2") (pintype "passive"))
    )
    (net (code "41") (name "P5V0_ADAC") (class "Default")
      (node (ref "R21") (pin "1") (pinfunction "1_1") (pintype "passive"))
    )
    (net (code "42") (name "P5V0_DDAC") (class "Default")
      (node (ref "R110") (pin "2") (pinfunction "2_2") (pintype "passive"))
      (node (ref "R17") (pin "2") (pinfunction "2_2") (pintype "passive"))
      (node (ref "R20") (pin "2") (pinfunction "2_2") (pintype "passive"))
      (node (ref "R23") (pin "2") (pinfunction "2_2") (pintype "passive"))
    )
    (net (code "43") (name "P11V0_ADAC") (class "Default")
      (node (ref "R18") (pin "1") (pinfunction "1_1") (pintype "passive"))
      (node (ref "R27") (pin "2") (pinfunction "2_2") (pintype "passive"))
      (node (ref "R28") (pin "1") (pinfunction "1_1") (pintype "passive"))
    )
    (net (code "44") (name "unconnected-(IC10-NC-Pad7)") (class "Default")
      (node (ref "IC10") (pin "7") (pinfunction "NC_7") (pintype "passive"))
    )
    (net (code "45") (name "unconnected-(IC10-NC-Pad10)") (class "Default")
      (node (ref "IC10") (pin "10") (pinfunction "NC_10") (pintype "passive"))
    )
    (net (code "46") (name "unconnected-(IC11A-RCM-Pad11)") (class "Default")
      (node (ref "IC11") (pin "11") (pinfunction "RCM_11") (pintype "input+no_connect"))
    )
    (net (code "47") (name "unconnected-(IC11A-RFB-Pad9)") (class "Default")
      (node (ref "IC11") (pin "9") (pinfunction "RFB_9") (pintype "input+no_connect"))
    )
    (net (code "48") (name "unconnected-(IC11A-ROFS-Pad10)") (class "Default")
      (node (ref "IC11") (pin "10") (pinfunction "ROFS_10") (pintype "input+no_connect"))
    )
    (net (code "49") (name "unconnected-(IC11C-NC-Pad1)") (class "Default")
      (node (ref "IC11") (pin "1") (pinfunction "NC_1") (pintype "passive"))
    )
    (net (code "50") (name "unconnected-(IC11C-NC-Pad12)") (class "Default")
      (node (ref "IC11") (pin "12") (pinfunction "NC_12") (pintype "passive"))
    )
    (net (code "51") (name "unconnected-(IC11C-NC-Pad13)") (class "Default")
      (node (ref "IC11") (pin "13") (pinfunction "NC_13") (pintype "passive"))
    )
    (net (code "52") (name "unconnected-(IC11C-NC-Pad15)") (class "Default")
      (node (ref "IC11") (pin "15") (pinfunction "NC_15") (pintype "passive"))
    )
    (net (code "53") (name "unconnected-(IC11C-NC-Pad24)") (class "Default")
      (node (ref "IC11") (pin "24") (pinfunction "NC_24") (pintype "passive"))
    )
    (net (code "54") (name "unconnected-(IC11C-NC-Pad25)") (class "Default")
      (node (ref "IC11") (pin "25") (pinfunction "NC_25") (pintype "passive"))
    )
    (net (code "55") (name "unconnected-(IC11C-NC-Pad29)") (class "Default")
      (node (ref "IC11") (pin "29") (pinfunction "NC_29") (pintype "passive"))
    )
    (net (code "56") (name "unconnected-(IC11C-NC-Pad36)") (class "Default")
      (node (ref "IC11") (pin "36") (pinfunction "NC_36") (pintype "passive"))
    )
    (net (code "57") (name "unconnected-(IC11C-NC-Pad37)") (class "Default")
      (node (ref "IC11") (pin "37") (pinfunction "NC_37") (pintype "passive"))
    )
    (net (code "58") (name "unconnected-(IC11C-NC-Pad48)") (class "Default")
      (node (ref "IC11") (pin "48") (pinfunction "NC_48") (pintype "passive"))
    )
    (net (code "59") (name "unconnected-(IC12-NC-Pad7)") (class "Default")
      (node (ref "IC12") (pin "7") (pinfunction "NC_7") (pintype "passive"))
    )
    (net (code "60") (name "unconnected-(IC12-NC-Pad10)") (class "Default")
      (node (ref "IC12") (pin "10") (pinfunction "NC_10") (pintype "passive"))
    )
    (net (code "61") (name "unconnected-(IC12-OUT1-Pad14)") (class "Default")
      (node (ref "IC12") (pin "14") (pinfunction "OUT1_14") (pintype "output"))
    )
    (net (code "62") (name "unconnected-(IC13B-V+-Pad8)") (class "Default")
      (node (ref "IC13") (pin "8") (pinfunction "V+_8") (pintype "power_in"))
    )
    (net (code "63") (name "unconnected-(IC13B-V--Pad4)") (class "Default")
      (node (ref "IC13") (pin "4") (pinfunction "V-_4") (pintype "power_in"))
    )
    (net (code "64") (name "unconnected-(IC14-NC-Pad1)") (class "Default")
      (node (ref "IC14") (pin "1") (pinfunction "NC_1") (pintype "passive"))
    )
    (net (code "65") (name "unconnected-(IC14-NC-Pad7)") (class "Default")
      (node (ref "IC14") (pin "7") (pinfunction "NC_7") (pintype "passive"))
    )
    (net (code "66") (name "unconnected-(IC14-NC-Pad8)") (class "Default")
      (node (ref "IC14") (pin "8") (pinfunction "NC_8") (pintype "passive"))
    )
    (net (code "67") (name "unconnected-(IC14-TEMP-Pad3)") (class "Default")
      (node (ref "IC14") (pin "3") (pinfunction "TEMP_3") (pintype "passive"))
    )
    (net (code "68") (name "unconnected-(IC14-TRIM-Pad5)") (class "Default")
      (node (ref "IC14") (pin "5") (pinfunction "TRIM_5") (pintype "passive"))
    )
  )
)
